# PCIE_-_mini-pcie-connector.net
KiCad netlist of a schematic drawn in Altium Designer
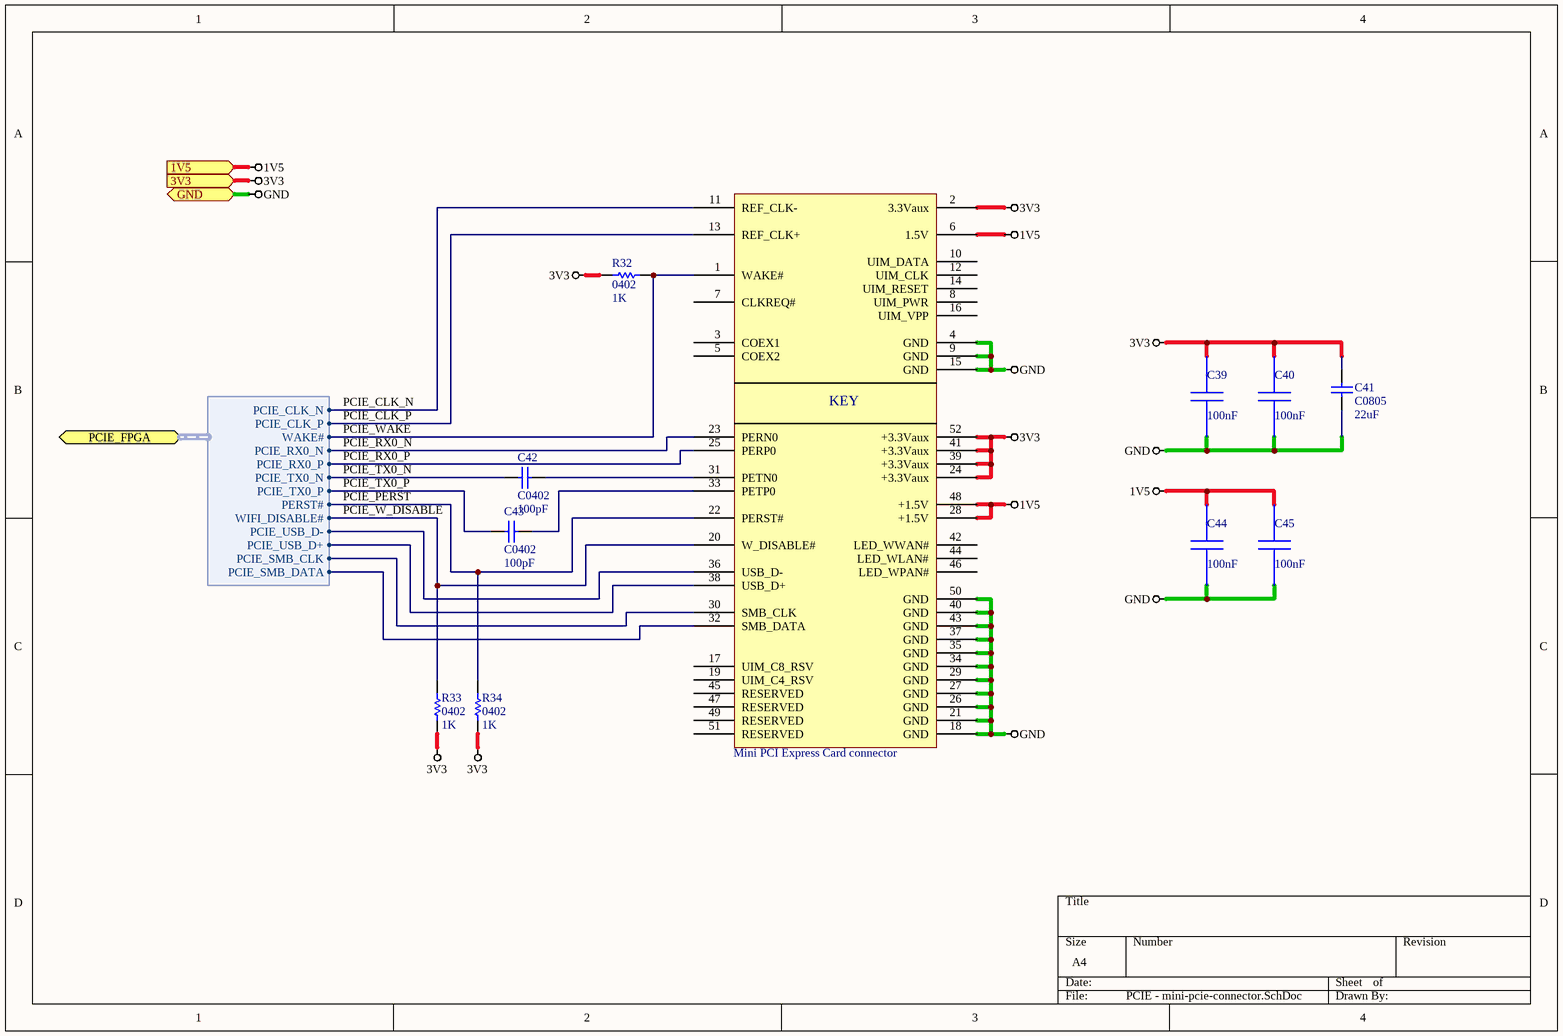
[diagram p0: PCIE - mini-pcie-connector.SchDoc]

(export (version "E")
  (design (tool "Eeschema 10.0.6"))
  (components
    (comp (ref "C39")
      (value "100nF")
      (footprint "C-0603")
      (description "C0603C104K3RACTU")
      (libsource (lib "TI WEBENCH") (part "Cinx"))
    )
    (comp (ref "C40")
      (value "100nF")
      (footprint "C-0603")
      (description "C0603C104K3RACTU")
      (libsource (lib "TI WEBENCH") (part "Cinx"))
    )
    (comp (ref "C41")
      (value "C0805")
      (footprint "C-0805")
      (description "Ceramic Chip Capacitor - Standard")
      (fields (field (name "ALTIUM_VALUE") "22uF") (field (name "PUBLISHER") "Altium Limited"))
      (libsource (lib "FPGA-pcie") (part "C0805"))
    )
    (comp (ref "C42")
      (value "C0402")
      (footprint "CAPC0402(1005)60_L")
      (description "Ceramic Chip Capacitor - Standard")
      (fields (field (name "ALTIUM_VALUE") "100pF") (field (name "PUBLISHER") "Altium Limited"))
      (libsource (lib "FPGA-pcie") (part "C0402"))
    )
    (comp (ref "C43")
      (value "C0402")
      (footprint "CAPC0402(1005)60_L")
      (description "Ceramic Chip Capacitor - Standard")
      (fields (field (name "ALTIUM_VALUE") "100pF") (field (name "PUBLISHER") "Altium Limited"))
      (libsource (lib "FPGA-pcie") (part "C0402"))
    )
    (comp (ref "C44")
      (value "100nF")
      (footprint "C-0603")
      (description "C0603C104K3RACTU")
      (libsource (lib "TI WEBENCH") (part "Cinx"))
    )
    (comp (ref "C45")
      (value "100nF")
      (footprint "C-0603")
      (description "C0603C104K3RACTU")
      (libsource (lib "TI WEBENCH") (part "Cinx"))
    )
    (comp (ref "CN1")
      (value "Mini PCI Express Card connector")
      (footprint "Mini PCI Express")
      (libsource (lib "mini-pcie") (part "MiniPCIe Card"))
    )
    (comp (ref "R32")
      (value "0402")
      (footprint "RESC0402(1005)40_L")
      (description "Resistor")
      (fields (field (name "ALTIUM_VALUE") "1K") (field (name "PUBLISHER") "Altium Limited"))
      (libsource (lib "Miscellaneous Devices") (part "Res1"))
    )
    (comp (ref "R33")
      (value "0402")
      (footprint "RESC0402(1005)40_L")
      (description "Resistor")
      (fields (field (name "ALTIUM_VALUE") "1K") (field (name "PUBLISHER") "Altium Limited"))
      (libsource (lib "Miscellaneous Devices") (part "Res1"))
    )
    (comp (ref "R34")
      (value "0402")
      (footprint "RESC0402(1005)40_L")
      (description "Resistor")
      (fields (field (name "ALTIUM_VALUE") "1K") (field (name "PUBLISHER") "Altium Limited"))
      (libsource (lib "Miscellaneous Devices") (part "Res1"))
    )
  )
  (nets
    (net (code "2") (name "/PCIE_CLK_N") (class "Default")
      (node (ref "CN1") (pin "11") (pinfunction "REF_CLK-_11") (pintype "passive"))
    )
    (net (code "3") (name "/PCIE_CLK_P") (class "Default")
      (node (ref "CN1") (pin "13") (pinfunction "REF_CLK+_13") (pintype "passive"))
    )
    (net (code "4") (name "/PCIE_PERST") (class "Default")
      (node (ref "CN1") (pin "22") (pinfunction "PERST#_22") (pintype "passive"))
      (node (ref "R34") (pin "2") (pinfunction "2_2") (pintype "passive"))
    )
    (net (code "5") (name "/PCIE_RX0_N") (class "Default")
      (node (ref "CN1") (pin "23") (pinfunction "PERN0_23") (pintype "passive"))
    )
    (net (code "6") (name "/PCIE_RX0_P") (class "Default")
      (node (ref "CN1") (pin "25") (pinfunction "PERP0_25") (pintype "passive"))
    )
    (net (code "7") (name "/PCIE_SMB_CLK") (class "Default")
      (node (ref "CN1") (pin "30") (pinfunction "SMB_CLK_30") (pintype "passive"))
    )
    (net (code "8") (name "/PCIE_SMB_DATA") (class "Default")
      (node (ref "CN1") (pin "32") (pinfunction "SMB_DATA_32") (pintype "passive"))
    )
    (net (code "9") (name "/PCIE_TX0_N") (class "Default")
      (node (ref "C42") (pin "1") (pinfunction "1_1") (pintype "passive"))
    )
    (net (code "10") (name "/PCIE_TX0_P") (class "Default")
      (node (ref "C43") (pin "1") (pinfunction "1_1") (pintype "passive"))
    )
    (net (code "11") (name "/PCIE_USB_D+") (class "Default")
      (node (ref "CN1") (pin "38") (pinfunction "USB_D+_38") (pintype "passive"))
    )
    (net (code "12") (name "/PCIE_USB_D-") (class "Default")
      (node (ref "CN1") (pin "36") (pinfunction "USB_D-_36") (pintype "passive"))
    )
    (net (code "13") (name "/PCIE_WAKE") (class "Default")
      (node (ref "CN1") (pin "1") (pinfunction "WAKE#_1") (pintype "passive"))
      (node (ref "R32") (pin "2") (pinfunction "2_2") (pintype "passive"))
    )
    (net (code "14") (name "/PCIE_W_DISABLE") (class "Default")
      (node (ref "CN1") (pin "20") (pinfunction "W_DISABLE#_20") (pintype "passive"))
      (node (ref "R33") (pin "2") (pinfunction "2_2") (pintype "passive"))
    )
    (net (code "16") (name "1V5") (class "Default")
      (node (ref "C44") (pin "1") (pinfunction "1_1") (pintype "passive"))
      (node (ref "C45") (pin "1") (pinfunction "1_1") (pintype "passive"))
      (node (ref "CN1") (pin "28") (pinfunction "+1.5V_28") (pintype "passive"))
      (node (ref "CN1") (pin "48") (pinfunction "+1.5V_48") (pintype "passive"))
      (node (ref "CN1") (pin "6") (pinfunction "1.5V_6") (pintype "passive"))
    )
    (net (code "17") (name "3V3") (class "Default")
      (node (ref "C39") (pin "1") (pinfunction "1_1") (pintype "passive"))
      (node (ref "C40") (pin "1") (pinfunction "1_1") (pintype "passive"))
      (node (ref "C41") (pin "2") (pinfunction "2_2") (pintype "passive"))
      (node (ref "CN1") (pin "2") (pinfunction "3.3Vaux_2") (pintype "passive"))
      (node (ref "CN1") (pin "24") (pinfunction "+3.3Vaux_24") (pintype "passive"))
      (node (ref "CN1") (pin "39") (pinfunction "+3.3Vaux_39") (pintype "passive"))
      (node (ref "CN1") (pin "41") (pinfunction "+3.3Vaux_41") (pintype "passive"))
      (node (ref "CN1") (pin "52") (pinfunction "+3.3Vaux_52") (pintype "passive"))
      (node (ref "R32") (pin "1") (pinfunction "1_1") (pintype "passive"))
      (node (ref "R33") (pin "1") (pinfunction "1_1") (pintype "passive"))
      (node (ref "R34") (pin "1") (pinfunction "1_1") (pintype "passive"))
    )
    (net (code "18") (name "GND") (class "Default")
      (node (ref "C39") (pin "2") (pinfunction "2_2") (pintype "passive"))
      (node (ref "C40") (pin "2") (pinfunction "2_2") (pintype "passive"))
      (node (ref "C41") (pin "1") (pinfunction "1_1") (pintype "passive"))
      (node (ref "C44") (pin "2") (pinfunction "2_2") (pintype "passive"))
      (node (ref "C45") (pin "2") (pinfunction "2_2") (pintype "passive"))
      (node (ref "CN1") (pin "15") (pinfunction "GND_15") (pintype "passive"))
      (node (ref "CN1") (pin "18") (pinfunction "GND_18") (pintype "passive"))
      (node (ref "CN1") (pin "21") (pinfunction "GND_21") (pintype "passive"))
      (node (ref "CN1") (pin "26") (pinfunction "GND_26") (pintype "passive"))
      (node (ref "CN1") (pin "27") (pinfunction "GND_27") (pintype "passive"))
      (node (ref "CN1") (pin "29") (pinfunction "GND_29") (pintype "passive"))
      (node (ref "CN1") (pin "34") (pinfunction "GND_34") (pintype "passive"))
      (node (ref "CN1") (pin "35") (pinfunction "GND_35") (pintype "passive"))
      (node (ref "CN1") (pin "37") (pinfunction "GND_37") (pintype "passive"))
      (node (ref "CN1") (pin "4") (pinfunction "GND_4") (pintype "passive"))
      (node (ref "CN1") (pin "40") (pinfunction "GND_40") (pintype "passive"))
      (node (ref "CN1") (pin "43") (pinfunction "GND_43") (pintype "passive"))
      (node (ref "CN1") (pin "50") (pinfunction "GND_50") (pintype "passive"))
      (node (ref "CN1") (pin "9") (pinfunction "GND_9") (pintype "passive"))
    )
    (net (code "19") (name "Net-(CN1-PETN0)") (class "Default")
      (node (ref "C42") (pin "2") (pinfunction "2_2") (pintype "passive"))
      (node (ref "CN1") (pin "31") (pinfunction "PETN0_31") (pintype "passive"))
    )
    (net (code "20") (name "Net-(CN1-PETP0)") (class "Default")
      (node (ref "C43") (pin "2") (pinfunction "2_2") (pintype "passive"))
      (node (ref "CN1") (pin "33") (pinfunction "PETP0_33") (pintype "passive"))
    )
    (net (code "21") (name "unconnected-(CN1-CLKREQ#-Pad7)") (class "Default")
      (node (ref "CN1") (pin "7") (pinfunction "CLKREQ#_7") (pintype "passive"))
    )
    (net (code "22") (name "unconnected-(CN1-COEX1-Pad3)") (class "Default")
      (node (ref "CN1") (pin "3") (pinfunction "COEX1_3") (pintype "passive"))
    )
    (net (code "23") (name "unconnected-(CN1-COEX2-Pad5)") (class "Default")
      (node (ref "CN1") (pin "5") (pinfunction "COEX2_5") (pintype "passive"))
    )
    (net (code "24") (name "unconnected-(CN1-LED_WLAN#-Pad44)") (class "Default")
      (node (ref "CN1") (pin "44") (pinfunction "LED_WLAN#_44") (pintype "passive"))
    )
    (net (code "25") (name "unconnected-(CN1-LED_WPAN#-Pad46)") (class "Default")
      (node (ref "CN1") (pin "46") (pinfunction "LED_WPAN#_46") (pintype "passive"))
    )
    (net (code "26") (name "unconnected-(CN1-LED_WWAN#-Pad42)") (class "Default")
      (node (ref "CN1") (pin "42") (pinfunction "LED_WWAN#_42") (pintype "passive"))
    )
    (net (code "27") (name "unconnected-(CN1-RESERVED-Pad45)") (class "Default")
      (node (ref "CN1") (pin "45") (pinfunction "RESERVED_45") (pintype "passive"))
    )
    (net (code "28") (name "unconnected-(CN1-RESERVED-Pad47)") (class "Default")
      (node (ref "CN1") (pin "47") (pinfunction "RESERVED_47") (pintype "passive"))
    )
    (net (code "29") (name "unconnected-(CN1-RESERVED-Pad49)") (class "Default")
      (node (ref "CN1") (pin "49") (pinfunction "RESERVED_49") (pintype "passive"))
    )
    (net (code "30") (name "unconnected-(CN1-RESERVED-Pad51)") (class "Default")
      (node (ref "CN1") (pin "51") (pinfunction "RESERVED_51") (pintype "passive"))
    )
    (net (code "31") (name "unconnected-(CN1-UIM_C4_RSV-Pad19)") (class "Default")
      (node (ref "CN1") (pin "19") (pinfunction "UIM_C4_RSV_19") (pintype "passive"))
    )
    (net (code "32") (name "unconnected-(CN1-UIM_C8_RSV-Pad17)") (class "Default")
      (node (ref "CN1") (pin "17") (pinfunction "UIM_C8_RSV_17") (pintype "passive"))
    )
    (net (code "33") (name "unconnected-(CN1-UIM_CLK-Pad12)") (class "Default")
      (node (ref "CN1") (pin "12") (pinfunction "UIM_CLK_12") (pintype "passive"))
    )
    (net (code "34") (name "unconnected-(CN1-UIM_DATA-Pad10)") (class "Default")
      (node (ref "CN1") (pin "10") (pinfunction "UIM_DATA_10") (pintype "passive"))
    )
    (net (code "35") (name "unconnected-(CN1-UIM_PWR-Pad8)") (class "Default")
      (node (ref "CN1") (pin "8") (pinfunction "UIM_PWR_8") (pintype "passive"))
    )
    (net (code "36") (name "unconnected-(CN1-UIM_RESET-Pad14)") (class "Default")
      (node (ref "CN1") (pin "14") (pinfunction "UIM_RESET_14") (pintype "passive"))
    )
    (net (code "37") (name "unconnected-(CN1-UIM_VPP-Pad16)") (class "Default")
      (node (ref "CN1") (pin "16") (pinfunction "UIM_VPP_16") (pintype "passive"))
    )
  )
)
